# Sheet5.net
KiCad netlist of a schematic drawn in Altium Designer
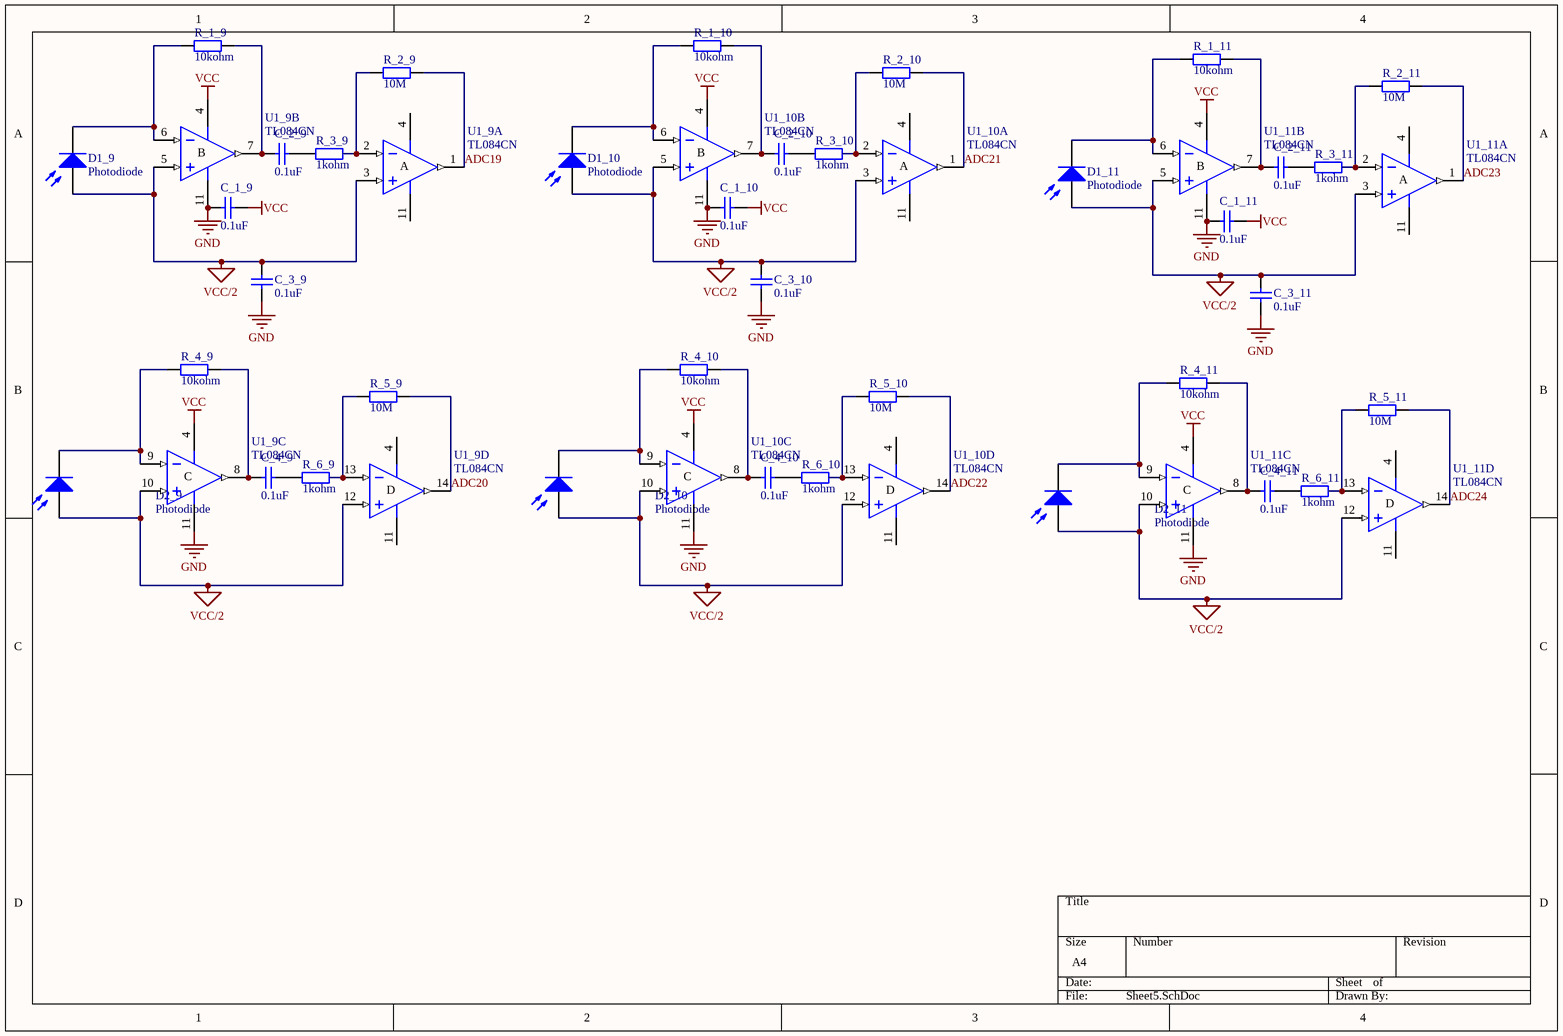
[diagram p0: Sheet5.SchDoc]

(export (version "E")
  (design (tool "Eeschema 10.0.6"))
  (components
    (comp (ref "C_1_9")
      (value "0.1uF")
      (footprint "cms805 - mini")
      (libsource (lib "lib_Robotronik") (part "Capa"))
    )
    (comp (ref "C_1_10")
      (value "0.1uF")
      (footprint "cms805 - mini")
      (libsource (lib "lib_Robotronik") (part "Capa"))
    )
    (comp (ref "C_1_11")
      (value "0.1uF")
      (footprint "cms805 - mini")
      (libsource (lib "lib_Robotronik") (part "Capa"))
    )
    (comp (ref "C_2_9")
      (value "0.1uF")
      (footprint "cms805 - mini")
      (libsource (lib "lib_Robotronik") (part "Capa"))
    )
    (comp (ref "C_2_10")
      (value "0.1uF")
      (footprint "cms805 - mini")
      (libsource (lib "lib_Robotronik") (part "Capa"))
    )
    (comp (ref "C_2_11")
      (value "0.1uF")
      (footprint "cms805 - mini")
      (libsource (lib "lib_Robotronik") (part "Capa"))
    )
    (comp (ref "C_3_9")
      (value "0.1uF")
      (footprint "cms805 - mini")
      (libsource (lib "lib_Robotronik") (part "Capa"))
    )
    (comp (ref "C_3_10")
      (value "0.1uF")
      (footprint "cms805 - mini")
      (libsource (lib "lib_Robotronik") (part "Capa"))
    )
    (comp (ref "C_3_11")
      (value "0.1uF")
      (footprint "cms805 - mini")
      (libsource (lib "lib_Robotronik") (part "Capa"))
    )
    (comp (ref "C_4_9")
      (value "0.1uF")
      (footprint "cms805 - mini")
      (libsource (lib "lib_Robotronik") (part "Capa"))
    )
    (comp (ref "C_4_10")
      (value "0.1uF")
      (footprint "cms805 - mini")
      (libsource (lib "lib_Robotronik") (part "Capa"))
    )
    (comp (ref "C_4_11")
      (value "0.1uF")
      (footprint "cms805 - mini")
      (libsource (lib "lib_Robotronik") (part "Capa"))
    )
    (comp (ref "D1_9")
      (value "Photodiode")
      (footprint "TEMD1000")
      (fields (field (name "PUBLISHER") "Altium Limited"))
      (libsource (lib "lib_Robotronik") (part "Photodiode"))
    )
    (comp (ref "D1_10")
      (value "Photodiode")
      (footprint "TEMD1000")
      (fields (field (name "PUBLISHER") "Altium Limited"))
      (libsource (lib "lib_Robotronik") (part "Photodiode"))
    )
    (comp (ref "D1_11")
      (value "Photodiode")
      (footprint "TEMD1000")
      (fields (field (name "PUBLISHER") "Altium Limited"))
      (libsource (lib "lib_Robotronik") (part "Photodiode"))
    )
    (comp (ref "D2_9")
      (value "Photodiode")
      (footprint "TEMD1000")
      (fields (field (name "PUBLISHER") "Altium Limited"))
      (libsource (lib "lib_Robotronik") (part "Photodiode"))
    )
    (comp (ref "D2_10")
      (value "Photodiode")
      (footprint "TEMD1000")
      (fields (field (name "PUBLISHER") "Altium Limited"))
      (libsource (lib "lib_Robotronik") (part "Photodiode"))
    )
    (comp (ref "D2_11")
      (value "Photodiode")
      (footprint "TEMD1000")
      (fields (field (name "PUBLISHER") "Altium Limited"))
      (libsource (lib "lib_Robotronik") (part "Photodiode"))
    )
    (comp (ref "R_1_9")
      (value "10kohm")
      (footprint "cms805 - mini")
      (libsource (lib "lib_Robotronik") (part "Resistance"))
    )
    (comp (ref "R_1_10")
      (value "10kohm")
      (footprint "cms805 - mini")
      (libsource (lib "lib_Robotronik") (part "Resistance"))
    )
    (comp (ref "R_1_11")
      (value "10kohm")
      (footprint "cms805 - mini")
      (libsource (lib "lib_Robotronik") (part "Resistance"))
    )
    (comp (ref "R_2_9")
      (value "10M")
      (footprint "cms805 - mini")
      (libsource (lib "lib_Robotronik") (part "Resistance"))
    )
    (comp (ref "R_2_10")
      (value "10M")
      (footprint "cms805 - mini")
      (libsource (lib "lib_Robotronik") (part "Resistance"))
    )
    (comp (ref "R_2_11")
      (value "10M")
      (footprint "cms805 - mini")
      (libsource (lib "lib_Robotronik") (part "Resistance"))
    )
    (comp (ref "R_3_9")
      (value "1kohm")
      (footprint "cms805 - mini")
      (libsource (lib "lib_Robotronik") (part "Resistance"))
    )
    (comp (ref "R_3_10")
      (value "1kohm")
      (footprint "cms805 - mini")
      (libsource (lib "lib_Robotronik") (part "Resistance"))
    )
    (comp (ref "R_3_11")
      (value "1kohm")
      (footprint "cms805 - mini")
      (libsource (lib "lib_Robotronik") (part "Resistance"))
    )
    (comp (ref "R_4_9")
      (value "10kohm")
      (footprint "cms805 - mini")
      (libsource (lib "lib_Robotronik") (part "Resistance"))
    )
    (comp (ref "R_4_10")
      (value "10kohm")
      (footprint "cms805 - mini")
      (libsource (lib "lib_Robotronik") (part "Resistance"))
    )
    (comp (ref "R_4_11")
      (value "10kohm")
      (footprint "cms805 - mini")
      (libsource (lib "lib_Robotronik") (part "Resistance"))
    )
    (comp (ref "R_5_9")
      (value "10M")
      (footprint "cms805 - mini")
      (libsource (lib "lib_Robotronik") (part "Resistance"))
    )
    (comp (ref "R_5_10")
      (value "10M")
      (footprint "cms805 - mini")
      (libsource (lib "lib_Robotronik") (part "Resistance"))
    )
    (comp (ref "R_5_11")
      (value "10M")
      (footprint "cms805 - mini")
      (libsource (lib "lib_Robotronik") (part "Resistance"))
    )
    (comp (ref "R_6_9")
      (value "1kohm")
      (footprint "cms805 - mini")
      (libsource (lib "lib_Robotronik") (part "Resistance"))
    )
    (comp (ref "R_6_10")
      (value "1kohm")
      (footprint "cms805 - mini")
      (libsource (lib "lib_Robotronik") (part "Resistance"))
    )
    (comp (ref "R_6_11")
      (value "1kohm")
      (footprint "cms805 - mini")
      (libsource (lib "lib_Robotronik") (part "Resistance"))
    )
    (comp (ref "U1_9")
      (value "TL084CN")
      (footprint "TSSOP14")
      (description "General-Purpose J-FET Quad Operational Amplifier")
      (fields (field (name "PUBLISHER") "Altium Limited"))
      (libsource (lib "lib_Robotronik") (part "TL084CN"))
    )
    (comp (ref "U1_10")
      (value "TL084CN")
      (footprint "TSSOP14")
      (description "General-Purpose J-FET Quad Operational Amplifier")
      (fields (field (name "PUBLISHER") "Altium Limited"))
      (libsource (lib "lib_Robotronik") (part "TL084CN"))
    )
    (comp (ref "U1_11")
      (value "TL084CN")
      (footprint "TSSOP14")
      (description "General-Purpose J-FET Quad Operational Amplifier")
      (fields (field (name "PUBLISHER") "Altium Limited"))
      (libsource (lib "lib_Robotronik") (part "TL084CN"))
    )
  )
  (nets
    (net (code "1") (name "/ADC19") (class "Default")
      (node (ref "R_2_9") (pin "2") (pinfunction "2_2") (pintype "passive"))
      (node (ref "U1_9") (pin "1") (pinfunction "OUT_1") (pintype "output"))
    )
    (net (code "2") (name "/ADC20") (class "Default")
      (node (ref "R_5_9") (pin "2") (pinfunction "2_2") (pintype "passive"))
      (node (ref "U1_9") (pin "14") (pinfunction "OUT_14") (pintype "output"))
    )
    (net (code "3") (name "/ADC21") (class "Default")
      (node (ref "R_2_10") (pin "2") (pinfunction "2_2") (pintype "passive"))
      (node (ref "U1_10") (pin "1") (pinfunction "OUT_1") (pintype "output"))
    )
    (net (code "4") (name "/ADC22") (class "Default")
      (node (ref "R_5_10") (pin "2") (pinfunction "2_2") (pintype "passive"))
      (node (ref "U1_10") (pin "14") (pinfunction "OUT_14") (pintype "output"))
    )
    (net (code "5") (name "/ADC23") (class "Default")
      (node (ref "R_2_11") (pin "2") (pinfunction "2_2") (pintype "passive"))
      (node (ref "U1_11") (pin "1") (pinfunction "OUT_1") (pintype "output"))
    )
    (net (code "6") (name "/ADC24") (class "Default")
      (node (ref "R_5_11") (pin "2") (pinfunction "2_2") (pintype "passive"))
      (node (ref "U1_11") (pin "14") (pinfunction "OUT_14") (pintype "output"))
    )
    (net (code "7") (name "GND") (class "Default")
      (node (ref "C_1_10") (pin "1") (pinfunction "1_1") (pintype "passive"))
      (node (ref "C_1_11") (pin "1") (pinfunction "1_1") (pintype "passive"))
      (node (ref "C_1_9") (pin "1") (pinfunction "1_1") (pintype "passive"))
      (node (ref "C_3_10") (pin "1") (pinfunction "1_1") (pintype "passive"))
      (node (ref "C_3_11") (pin "1") (pinfunction "1_1") (pintype "passive"))
      (node (ref "C_3_9") (pin "1") (pinfunction "1_1") (pintype "passive"))
      (node (ref "U1_10") (pin "11") (pinfunction "V-_11") (pintype "power_in"))
      (node (ref "U1_11") (pin "11") (pinfunction "V-_11") (pintype "power_in"))
      (node (ref "U1_9") (pin "11") (pinfunction "V-_11") (pintype "power_in"))
    )
    (net (code "8") (name "Net-(C_2_9-Pad1)") (class "Default")
      (node (ref "C_2_9") (pin "1") (pinfunction "1_1") (pintype "passive"))
      (node (ref "R_3_9") (pin "1") (pinfunction "1_1") (pintype "passive"))
    )
    (net (code "9") (name "Net-(C_2_10-Pad1)") (class "Default")
      (node (ref "C_2_10") (pin "1") (pinfunction "1_1") (pintype "passive"))
      (node (ref "R_3_10") (pin "1") (pinfunction "1_1") (pintype "passive"))
    )
    (net (code "10") (name "Net-(C_2_11-Pad1)") (class "Default")
      (node (ref "C_2_11") (pin "1") (pinfunction "1_1") (pintype "passive"))
      (node (ref "R_3_11") (pin "1") (pinfunction "1_1") (pintype "passive"))
    )
    (net (code "11") (name "Net-(C_4_9-Pad1)") (class "Default")
      (node (ref "C_4_9") (pin "1") (pinfunction "1_1") (pintype "passive"))
      (node (ref "R_6_9") (pin "1") (pinfunction "1_1") (pintype "passive"))
    )
    (net (code "12") (name "Net-(C_4_10-Pad1)") (class "Default")
      (node (ref "C_4_10") (pin "1") (pinfunction "1_1") (pintype "passive"))
      (node (ref "R_6_10") (pin "1") (pinfunction "1_1") (pintype "passive"))
    )
    (net (code "13") (name "Net-(C_4_11-Pad1)") (class "Default")
      (node (ref "C_4_11") (pin "1") (pinfunction "1_1") (pintype "passive"))
      (node (ref "R_6_11") (pin "1") (pinfunction "1_1") (pintype "passive"))
    )
    (net (code "14") (name "Net-(D1_9-K)") (class "Default")
      (node (ref "D1_9") (pin "2") (pinfunction "K_2") (pintype "passive"))
      (node (ref "R_1_9") (pin "1") (pinfunction "1_1") (pintype "passive"))
      (node (ref "U1_9") (pin "6") (pinfunction "IN-_6") (pintype "input"))
    )
    (net (code "15") (name "Net-(D1_10-K)") (class "Default")
      (node (ref "D1_10") (pin "2") (pinfunction "K_2") (pintype "passive"))
      (node (ref "R_1_10") (pin "1") (pinfunction "1_1") (pintype "passive"))
      (node (ref "U1_10") (pin "6") (pinfunction "IN-_6") (pintype "input"))
    )
    (net (code "16") (name "Net-(D1_11-K)") (class "Default")
      (node (ref "D1_11") (pin "2") (pinfunction "K_2") (pintype "passive"))
      (node (ref "R_1_11") (pin "1") (pinfunction "1_1") (pintype "passive"))
      (node (ref "U1_11") (pin "6") (pinfunction "IN-_6") (pintype "input"))
    )
    (net (code "17") (name "Net-(D2_9-K)") (class "Default")
      (node (ref "D2_9") (pin "2") (pinfunction "K_2") (pintype "passive"))
      (node (ref "R_4_9") (pin "1") (pinfunction "1_1") (pintype "passive"))
      (node (ref "U1_9") (pin "9") (pinfunction "IN-_9") (pintype "input"))
    )
    (net (code "18") (name "Net-(D2_10-K)") (class "Default")
      (node (ref "D2_10") (pin "2") (pinfunction "K_2") (pintype "passive"))
      (node (ref "R_4_10") (pin "1") (pinfunction "1_1") (pintype "passive"))
      (node (ref "U1_10") (pin "9") (pinfunction "IN-_9") (pintype "input"))
    )
    (net (code "19") (name "Net-(D2_11-K)") (class "Default")
      (node (ref "D2_11") (pin "2") (pinfunction "K_2") (pintype "passive"))
      (node (ref "R_4_11") (pin "1") (pinfunction "1_1") (pintype "passive"))
      (node (ref "U1_11") (pin "9") (pinfunction "IN-_9") (pintype "input"))
    )
    (net (code "20") (name "Net-(U1_9A-IN-)") (class "Default")
      (node (ref "R_2_9") (pin "1") (pinfunction "1_1") (pintype "passive"))
      (node (ref "R_3_9") (pin "2") (pinfunction "2_2") (pintype "passive"))
      (node (ref "U1_9") (pin "2") (pinfunction "IN-_2") (pintype "input"))
    )
    (net (code "21") (name "Net-(U1_9B-OUT)") (class "Default")
      (node (ref "C_2_9") (pin "2") (pinfunction "2_2") (pintype "passive"))
      (node (ref "R_1_9") (pin "2") (pinfunction "2_2") (pintype "passive"))
      (node (ref "U1_9") (pin "7") (pinfunction "OUT_7") (pintype "output"))
    )
    (net (code "22") (name "Net-(U1_9C-OUT)") (class "Default")
      (node (ref "C_4_9") (pin "2") (pinfunction "2_2") (pintype "passive"))
      (node (ref "R_4_9") (pin "2") (pinfunction "2_2") (pintype "passive"))
      (node (ref "U1_9") (pin "8") (pinfunction "OUT_8") (pintype "output"))
    )
    (net (code "23") (name "Net-(U1_9D-IN-)") (class "Default")
      (node (ref "R_5_9") (pin "1") (pinfunction "1_1") (pintype "passive"))
      (node (ref "R_6_9") (pin "2") (pinfunction "2_2") (pintype "passive"))
      (node (ref "U1_9") (pin "13") (pinfunction "IN-_13") (pintype "input"))
    )
    (net (code "24") (name "Net-(U1_10A-IN-)") (class "Default")
      (node (ref "R_2_10") (pin "1") (pinfunction "1_1") (pintype "passive"))
      (node (ref "R_3_10") (pin "2") (pinfunction "2_2") (pintype "passive"))
      (node (ref "U1_10") (pin "2") (pinfunction "IN-_2") (pintype "input"))
    )
    (net (code "25") (name "Net-(U1_10B-OUT)") (class "Default")
      (node (ref "C_2_10") (pin "2") (pinfunction "2_2") (pintype "passive"))
      (node (ref "R_1_10") (pin "2") (pinfunction "2_2") (pintype "passive"))
      (node (ref "U1_10") (pin "7") (pinfunction "OUT_7") (pintype "output"))
    )
    (net (code "26") (name "Net-(U1_10C-OUT)") (class "Default")
      (node (ref "C_4_10") (pin "2") (pinfunction "2_2") (pintype "passive"))
      (node (ref "R_4_10") (pin "2") (pinfunction "2_2") (pintype "passive"))
      (node (ref "U1_10") (pin "8") (pinfunction "OUT_8") (pintype "output"))
    )
    (net (code "27") (name "Net-(U1_10D-IN-)") (class "Default")
      (node (ref "R_5_10") (pin "1") (pinfunction "1_1") (pintype "passive"))
      (node (ref "R_6_10") (pin "2") (pinfunction "2_2") (pintype "passive"))
      (node (ref "U1_10") (pin "13") (pinfunction "IN-_13") (pintype "input"))
    )
    (net (code "28") (name "Net-(U1_11A-IN-)") (class "Default")
      (node (ref "R_2_11") (pin "1") (pinfunction "1_1") (pintype "passive"))
      (node (ref "R_3_11") (pin "2") (pinfunction "2_2") (pintype "passive"))
      (node (ref "U1_11") (pin "2") (pinfunction "IN-_2") (pintype "input"))
    )
    (net (code "29") (name "Net-(U1_11B-OUT)") (class "Default")
      (node (ref "C_2_11") (pin "2") (pinfunction "2_2") (pintype "passive"))
      (node (ref "R_1_11") (pin "2") (pinfunction "2_2") (pintype "passive"))
      (node (ref "U1_11") (pin "7") (pinfunction "OUT_7") (pintype "output"))
    )
    (net (code "30") (name "Net-(U1_11C-OUT)") (class "Default")
      (node (ref "C_4_11") (pin "2") (pinfunction "2_2") (pintype "passive"))
      (node (ref "R_4_11") (pin "2") (pinfunction "2_2") (pintype "passive"))
      (node (ref "U1_11") (pin "8") (pinfunction "OUT_8") (pintype "output"))
    )
    (net (code "31") (name "Net-(U1_11D-IN-)") (class "Default")
      (node (ref "R_5_11") (pin "1") (pinfunction "1_1") (pintype "passive"))
      (node (ref "R_6_11") (pin "2") (pinfunction "2_2") (pintype "passive"))
      (node (ref "U1_11") (pin "13") (pinfunction "IN-_13") (pintype "input"))
    )
    (net (code "32") (name "VCC") (class "Default")
      (node (ref "C_1_10") (pin "2") (pinfunction "2_2") (pintype "passive"))
      (node (ref "C_1_11") (pin "2") (pinfunction "2_2") (pintype "passive"))
      (node (ref "C_1_9") (pin "2") (pinfunction "2_2") (pintype "passive"))
      (node (ref "U1_10") (pin "4") (pinfunction "V+_4") (pintype "power_in"))
      (node (ref "U1_11") (pin "4") (pinfunction "V+_4") (pintype "power_in"))
      (node (ref "U1_9") (pin "4") (pinfunction "V+_4") (pintype "power_in"))
    )
    (net (code "33") (name "VCC{slash}2") (class "Default")
      (node (ref "C_3_10") (pin "2") (pinfunction "2_2") (pintype "passive"))
      (node (ref "C_3_11") (pin "2") (pinfunction "2_2") (pintype "passive"))
      (node (ref "C_3_9") (pin "2") (pinfunction "2_2") (pintype "passive"))
      (node (ref "D1_10") (pin "1") (pinfunction "A_1") (pintype "passive"))
      (node (ref "D1_11") (pin "1") (pinfunction "A_1") (pintype "passive"))
      (node (ref "D1_9") (pin "1") (pinfunction "A_1") (pintype "passive"))
      (node (ref "D2_10") (pin "1") (pinfunction "A_1") (pintype "passive"))
      (node (ref "D2_11") (pin "1") (pinfunction "A_1") (pintype "passive"))
      (node (ref "D2_9") (pin "1") (pinfunction "A_1") (pintype "passive"))
      (node (ref "U1_10") (pin "10") (pinfunction "IN+_10") (pintype "input"))
      (node (ref "U1_10") (pin "12") (pinfunction "IN+_12") (pintype "input"))
      (node (ref "U1_10") (pin "3") (pinfunction "IN+_3") (pintype "input"))
      (node (ref "U1_10") (pin "5") (pinfunction "IN+_5") (pintype "input"))
      (node (ref "U1_11") (pin "10") (pinfunction "IN+_10") (pintype "input"))
      (node (ref "U1_11") (pin "12") (pinfunction "IN+_12") (pintype "input"))
      (node (ref "U1_11") (pin "3") (pinfunction "IN+_3") (pintype "input"))
      (node (ref "U1_11") (pin "5") (pinfunction "IN+_5") (pintype "input"))
      (node (ref "U1_9") (pin "10") (pinfunction "IN+_10") (pintype "input"))
      (node (ref "U1_9") (pin "12") (pinfunction "IN+_12") (pintype "input"))
      (node (ref "U1_9") (pin "3") (pinfunction "IN+_3") (pintype "input"))
      (node (ref "U1_9") (pin "5") (pinfunction "IN+_5") (pintype "input"))
    )
    (net (code "34") (name "unconnected-(U1_9A-V+-Pad4)") (class "Default")
      (node (ref "U1_9") (pin "4") (pinfunction "V+_4") (pintype "power_in"))
    )
    (net (code "35") (name "unconnected-(U1_9A-V--Pad11)") (class "Default")
      (node (ref "U1_9") (pin "11") (pinfunction "V-_11") (pintype "power_in"))
    )
    (net (code "36") (name "unconnected-(U1_9D-V+-Pad4)") (class "Default")
      (node (ref "U1_9") (pin "4") (pinfunction "V+_4") (pintype "power_in"))
    )
    (net (code "37") (name "unconnected-(U1_9D-V--Pad11)") (class "Default")
      (node (ref "U1_9") (pin "11") (pinfunction "V-_11") (pintype "power_in"))
    )
    (net (code "38") (name "unconnected-(U1_10A-V+-Pad4)") (class "Default")
      (node (ref "U1_10") (pin "4") (pinfunction "V+_4") (pintype "power_in"))
    )
    (net (code "39") (name "unconnected-(U1_10A-V--Pad11)") (class "Default")
      (node (ref "U1_10") (pin "11") (pinfunction "V-_11") (pintype "power_in"))
    )
    (net (code "40") (name "unconnected-(U1_10D-V+-Pad4)") (class "Default")
      (node (ref "U1_10") (pin "4") (pinfunction "V+_4") (pintype "power_in"))
    )
    (net (code "41") (name "unconnected-(U1_10D-V--Pad11)") (class "Default")
      (node (ref "U1_10") (pin "11") (pinfunction "V-_11") (pintype "power_in"))
    )
    (net (code "42") (name "unconnected-(U1_11A-V+-Pad4)") (class "Default")
      (node (ref "U1_11") (pin "4") (pinfunction "V+_4") (pintype "power_in"))
    )
    (net (code "43") (name "unconnected-(U1_11A-V--Pad11)") (class "Default")
      (node (ref "U1_11") (pin "11") (pinfunction "V-_11") (pintype "power_in"))
    )
    (net (code "44") (name "unconnected-(U1_11D-V+-Pad4)") (class "Default")
      (node (ref "U1_11") (pin "4") (pinfunction "V+_4") (pintype "power_in"))
    )
    (net (code "45") (name "unconnected-(U1_11D-V--Pad11)") (class "Default")
      (node (ref "U1_11") (pin "11") (pinfunction "V-_11") (pintype "power_in"))
    )
  )
)
